# task_3.net
KiCad netlist of a schematic drawn in EAGLE
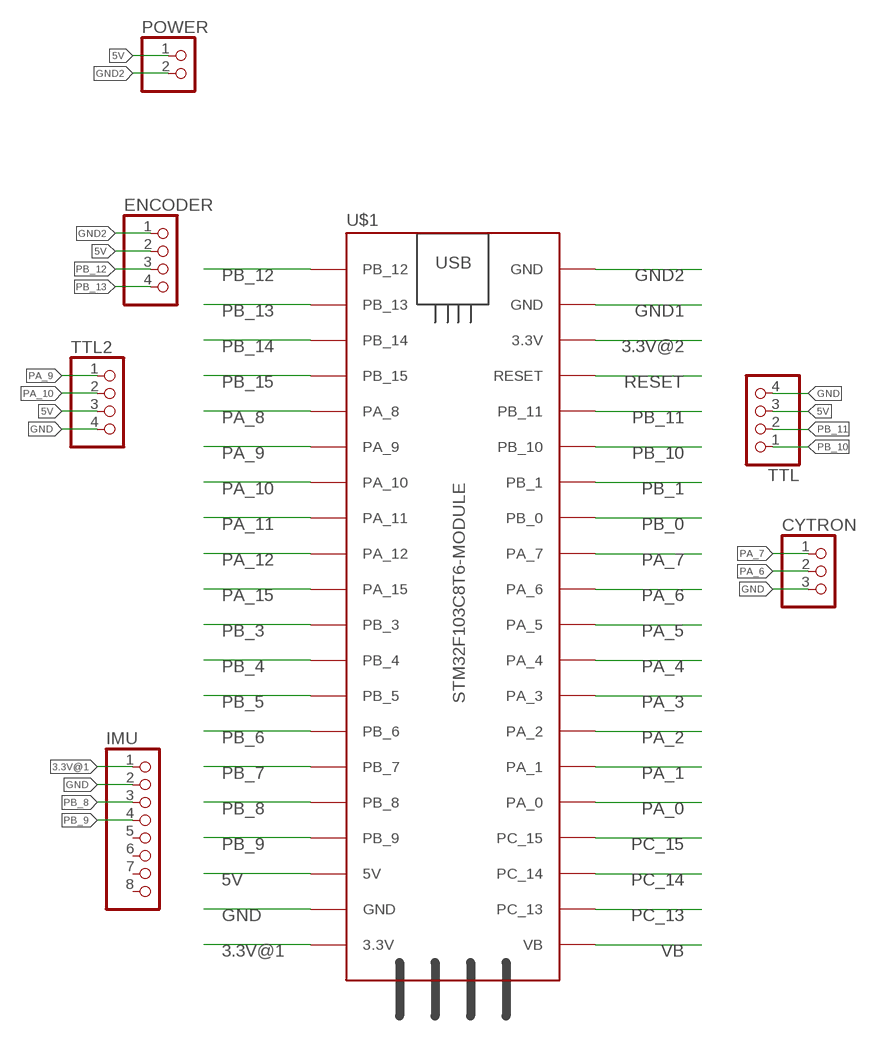
[diagram p0: schematic, sheet 1]

(export (version "E")
  (design (tool "Eeschema 10.0.6"))
  (components
    (comp (ref "CYTRON")
      (value "PINHD-3_DATA")
      (footprint "eagle-import:1X03_DATA")
      (libsource (lib "eagle-import") (part "PINHD-3_DATA"))
    )
    (comp (ref "ENCODER")
      (value "PINHD-4_DATA")
      (footprint "eagle-import:1X04_DATA")
      (libsource (lib "eagle-import") (part "PINHD-4_DATA"))
    )
    (comp (ref "IMU")
      (value "PINHD-1X8")
      (footprint "eagle-import:1X08")
      (libsource (lib "eagle-import") (part "PINHD-1X8"))
    )
    (comp (ref "POWER")
      (value "PINHD-2_DATA")
      (footprint "eagle-import:1X02_DATA")
      (libsource (lib "eagle-import") (part "PINHD-2_DATA"))
    )
    (comp (ref "TTL")
      (value "PINHD-4_DATA")
      (footprint "eagle-import:1X04_DATA")
      (libsource (lib "eagle-import") (part "PINHD-4_DATA"))
    )
    (comp (ref "TTL2")
      (value "PINHD-4_DATA")
      (footprint "eagle-import:1X04_DATA")
      (libsource (lib "eagle-import") (part "PINHD-4_DATA"))
    )
    (comp (ref "U$1")
      (value "STM32F103C8T6-MODULE")
      (footprint "eagle-import:STM32F103C8T6-MODULE")
      (libsource (lib "eagle-import") (part "STM32F103C8T6-MODULE"))
    )
  )
  (nets
    (net (code "1") (name "/3.3V@2") (class "Default")
      (node (ref "U$1") (pin "3.3V_2") (pinfunction "3.3V_3.3V_2") (pintype "bidirectional"))
    )
    (net (code "2") (name "/GND1") (class "Default")
      (node (ref "U$1") (pin "GND_2") (pinfunction "GND_GND_2") (pintype "bidirectional"))
    )
    (net (code "3") (name "/PA_0") (class "Default")
      (node (ref "U$1") (pin "PA_0") (pinfunction "PA_0_PA_0") (pintype "bidirectional"))
    )
    (net (code "4") (name "/PA_1") (class "Default")
      (node (ref "U$1") (pin "PA_1") (pinfunction "PA_1_PA_1") (pintype "bidirectional"))
    )
    (net (code "5") (name "/PA_2") (class "Default")
      (node (ref "U$1") (pin "PA_2") (pinfunction "PA_2_PA_2") (pintype "bidirectional"))
    )
    (net (code "6") (name "/PA_3") (class "Default")
      (node (ref "U$1") (pin "PA_3") (pinfunction "PA_3_PA_3") (pintype "bidirectional"))
    )
    (net (code "7") (name "/PA_4") (class "Default")
      (node (ref "U$1") (pin "PA_4") (pinfunction "PA_4_PA_4") (pintype "bidirectional"))
    )
    (net (code "8") (name "/PA_5") (class "Default")
      (node (ref "U$1") (pin "PA_5") (pinfunction "PA_5_PA_5") (pintype "bidirectional"))
    )
    (net (code "9") (name "/PA_8") (class "Default")
      (node (ref "U$1") (pin "PA_8") (pinfunction "PA_8_PA_8") (pintype "bidirectional"))
    )
    (net (code "10") (name "/PA_11") (class "Default")
      (node (ref "U$1") (pin "PA_11") (pinfunction "PA_11_PA_11") (pintype "bidirectional"))
    )
    (net (code "11") (name "/PA_12") (class "Default")
      (node (ref "U$1") (pin "PA_12") (pinfunction "PA_12_PA_12") (pintype "bidirectional"))
    )
    (net (code "12") (name "/PA_15") (class "Default")
      (node (ref "U$1") (pin "PA_15") (pinfunction "PA_15_PA_15") (pintype "bidirectional"))
    )
    (net (code "13") (name "/PB_0") (class "Default")
      (node (ref "U$1") (pin "PB_0") (pinfunction "PB_0_PB_0") (pintype "bidirectional"))
    )
    (net (code "14") (name "/PB_1") (class "Default")
      (node (ref "U$1") (pin "PB_1") (pinfunction "PB_1_PB_1") (pintype "bidirectional"))
    )
    (net (code "15") (name "/PB_3") (class "Default")
      (node (ref "U$1") (pin "PB_3") (pinfunction "PB_3_PB_3") (pintype "bidirectional"))
    )
    (net (code "16") (name "/PB_4") (class "Default")
      (node (ref "U$1") (pin "PB_4") (pinfunction "PB_4_PB_4") (pintype "bidirectional"))
    )
    (net (code "17") (name "/PB_5") (class "Default")
      (node (ref "U$1") (pin "PB_5") (pinfunction "PB_5_PB_5") (pintype "bidirectional"))
    )
    (net (code "18") (name "/PB_6") (class "Default")
      (node (ref "U$1") (pin "PB_6") (pinfunction "PB_6_PB_6") (pintype "bidirectional"))
    )
    (net (code "19") (name "/PB_7") (class "Default")
      (node (ref "U$1") (pin "PB_7") (pinfunction "PB_7_PB_7") (pintype "bidirectional"))
    )
    (net (code "20") (name "/PB_14") (class "Default")
      (node (ref "U$1") (pin "PB_14") (pinfunction "PB_14_PB_14") (pintype "bidirectional"))
    )
    (net (code "21") (name "/PB_15") (class "Default")
      (node (ref "U$1") (pin "PB_15") (pinfunction "PB_15_PB_15") (pintype "bidirectional"))
    )
    (net (code "22") (name "/PC_13") (class "Default")
      (node (ref "U$1") (pin "PC_13") (pinfunction "PC_13_PC_13") (pintype "bidirectional"))
    )
    (net (code "23") (name "/PC_14") (class "Default")
      (node (ref "U$1") (pin "PC_14") (pinfunction "PC_14_PC_14") (pintype "bidirectional"))
    )
    (net (code "24") (name "/PC_15") (class "Default")
      (node (ref "U$1") (pin "PC_15") (pinfunction "PC_15_PC_15") (pintype "bidirectional"))
    )
    (net (code "25") (name "/RESET") (class "Default")
      (node (ref "U$1") (pin "RESET") (pinfunction "RESET_RESET") (pintype "bidirectional"))
    )
    (net (code "26") (name "/VB") (class "Default")
      (node (ref "U$1") (pin "VB") (pinfunction "VB_VB") (pintype "bidirectional"))
    )
    (net (code "27") (name "3.3V@1") (class "Default")
      (node (ref "IMU") (pin "1") (pinfunction "1_1") (pintype "passive"))
      (node (ref "U$1") (pin "3.3V_1") (pinfunction "3.3V_3.3V_1") (pintype "bidirectional"))
    )
    (net (code "28") (name "5V") (class "Default")
      (node (ref "ENCODER") (pin "2") (pinfunction "2_2") (pintype "passive"))
      (node (ref "POWER") (pin "1") (pinfunction "1_1") (pintype "passive"))
      (node (ref "TTL") (pin "3") (pinfunction "3_3") (pintype "passive"))
      (node (ref "TTL2") (pin "3") (pinfunction "3_3") (pintype "passive"))
      (node (ref "U$1") (pin "5V") (pinfunction "5V_5V") (pintype "bidirectional"))
    )
    (net (code "29") (name "GND") (class "Default")
      (node (ref "CYTRON") (pin "3") (pinfunction "3_3") (pintype "passive"))
      (node (ref "IMU") (pin "2") (pinfunction "2_2") (pintype "passive"))
      (node (ref "TTL") (pin "4") (pinfunction "4_4") (pintype "passive"))
      (node (ref "TTL2") (pin "4") (pinfunction "4_4") (pintype "passive"))
      (node (ref "U$1") (pin "GND_1") (pinfunction "GND_GND_1") (pintype "bidirectional"))
    )
    (net (code "30") (name "GND2") (class "Default")
      (node (ref "ENCODER") (pin "1") (pinfunction "1_1") (pintype "passive"))
      (node (ref "POWER") (pin "2") (pinfunction "2_2") (pintype "passive"))
      (node (ref "U$1") (pin "GND_3") (pinfunction "GND_GND_3") (pintype "power_in"))
    )
    (net (code "31") (name "PA_6") (class "Default")
      (node (ref "CYTRON") (pin "2") (pinfunction "2_2") (pintype "passive"))
      (node (ref "U$1") (pin "PA_6") (pinfunction "PA_6_PA_6") (pintype "bidirectional"))
    )
    (net (code "32") (name "PA_7") (class "Default")
      (node (ref "CYTRON") (pin "1") (pinfunction "1_1") (pintype "passive"))
      (node (ref "U$1") (pin "PA_7") (pinfunction "PA_7_PA_7") (pintype "bidirectional"))
    )
    (net (code "33") (name "PA_9") (class "Default")
      (node (ref "TTL2") (pin "1") (pinfunction "1_1") (pintype "passive"))
      (node (ref "U$1") (pin "PA_9") (pinfunction "PA_9_PA_9") (pintype "bidirectional"))
    )
    (net (code "34") (name "PA_10") (class "Default")
      (node (ref "TTL2") (pin "2") (pinfunction "2_2") (pintype "passive"))
      (node (ref "U$1") (pin "PA_10") (pinfunction "PA_10_PA_10") (pintype "bidirectional"))
    )
    (net (code "35") (name "PB_8") (class "Default")
      (node (ref "IMU") (pin "3") (pinfunction "3_3") (pintype "passive"))
      (node (ref "U$1") (pin "PB_8") (pinfunction "PB_8_PB_8") (pintype "bidirectional"))
    )
    (net (code "36") (name "PB_9") (class "Default")
      (node (ref "IMU") (pin "4") (pinfunction "4_4") (pintype "passive"))
      (node (ref "U$1") (pin "PB_9") (pinfunction "PB_9_PB_9") (pintype "bidirectional"))
    )
    (net (code "37") (name "PB_10") (class "Default")
      (node (ref "TTL") (pin "1") (pinfunction "1_1") (pintype "passive"))
      (node (ref "U$1") (pin "PB_10") (pinfunction "PB_10_PB_10") (pintype "bidirectional"))
    )
    (net (code "38") (name "PB_11") (class "Default")
      (node (ref "TTL") (pin "2") (pinfunction "2_2") (pintype "passive"))
      (node (ref "U$1") (pin "PB_11") (pinfunction "PB_11_PB_11") (pintype "bidirectional"))
    )
    (net (code "39") (name "PB_12") (class "Default")
      (node (ref "ENCODER") (pin "3") (pinfunction "3_3") (pintype "passive"))
      (node (ref "U$1") (pin "PB_12") (pinfunction "PB_12_PB_12") (pintype "bidirectional"))
    )
    (net (code "40") (name "PB_13") (class "Default")
      (node (ref "ENCODER") (pin "4") (pinfunction "4_4") (pintype "passive"))
      (node (ref "U$1") (pin "PB_13") (pinfunction "PB_13_PB_13") (pintype "bidirectional"))
    )
    (net (code "41") (name "unconnected-(IMU-Pad5)") (class "Default")
      (node (ref "IMU") (pin "5") (pinfunction "5_5") (pintype "passive"))
    )
    (net (code "42") (name "unconnected-(IMU-Pad6)") (class "Default")
      (node (ref "IMU") (pin "6") (pinfunction "6_6") (pintype "passive"))
    )
    (net (code "43") (name "unconnected-(IMU-Pad7)") (class "Default")
      (node (ref "IMU") (pin "7") (pinfunction "7_7") (pintype "passive"))
    )
    (net (code "44") (name "unconnected-(IMU-Pad8)") (class "Default")
      (node (ref "IMU") (pin "8") (pinfunction "8_8") (pintype "passive"))
    )
  )
)
